# Uuu_sourcefile.net
KiCad netlist of a schematic drawn in EasyEDA Pro
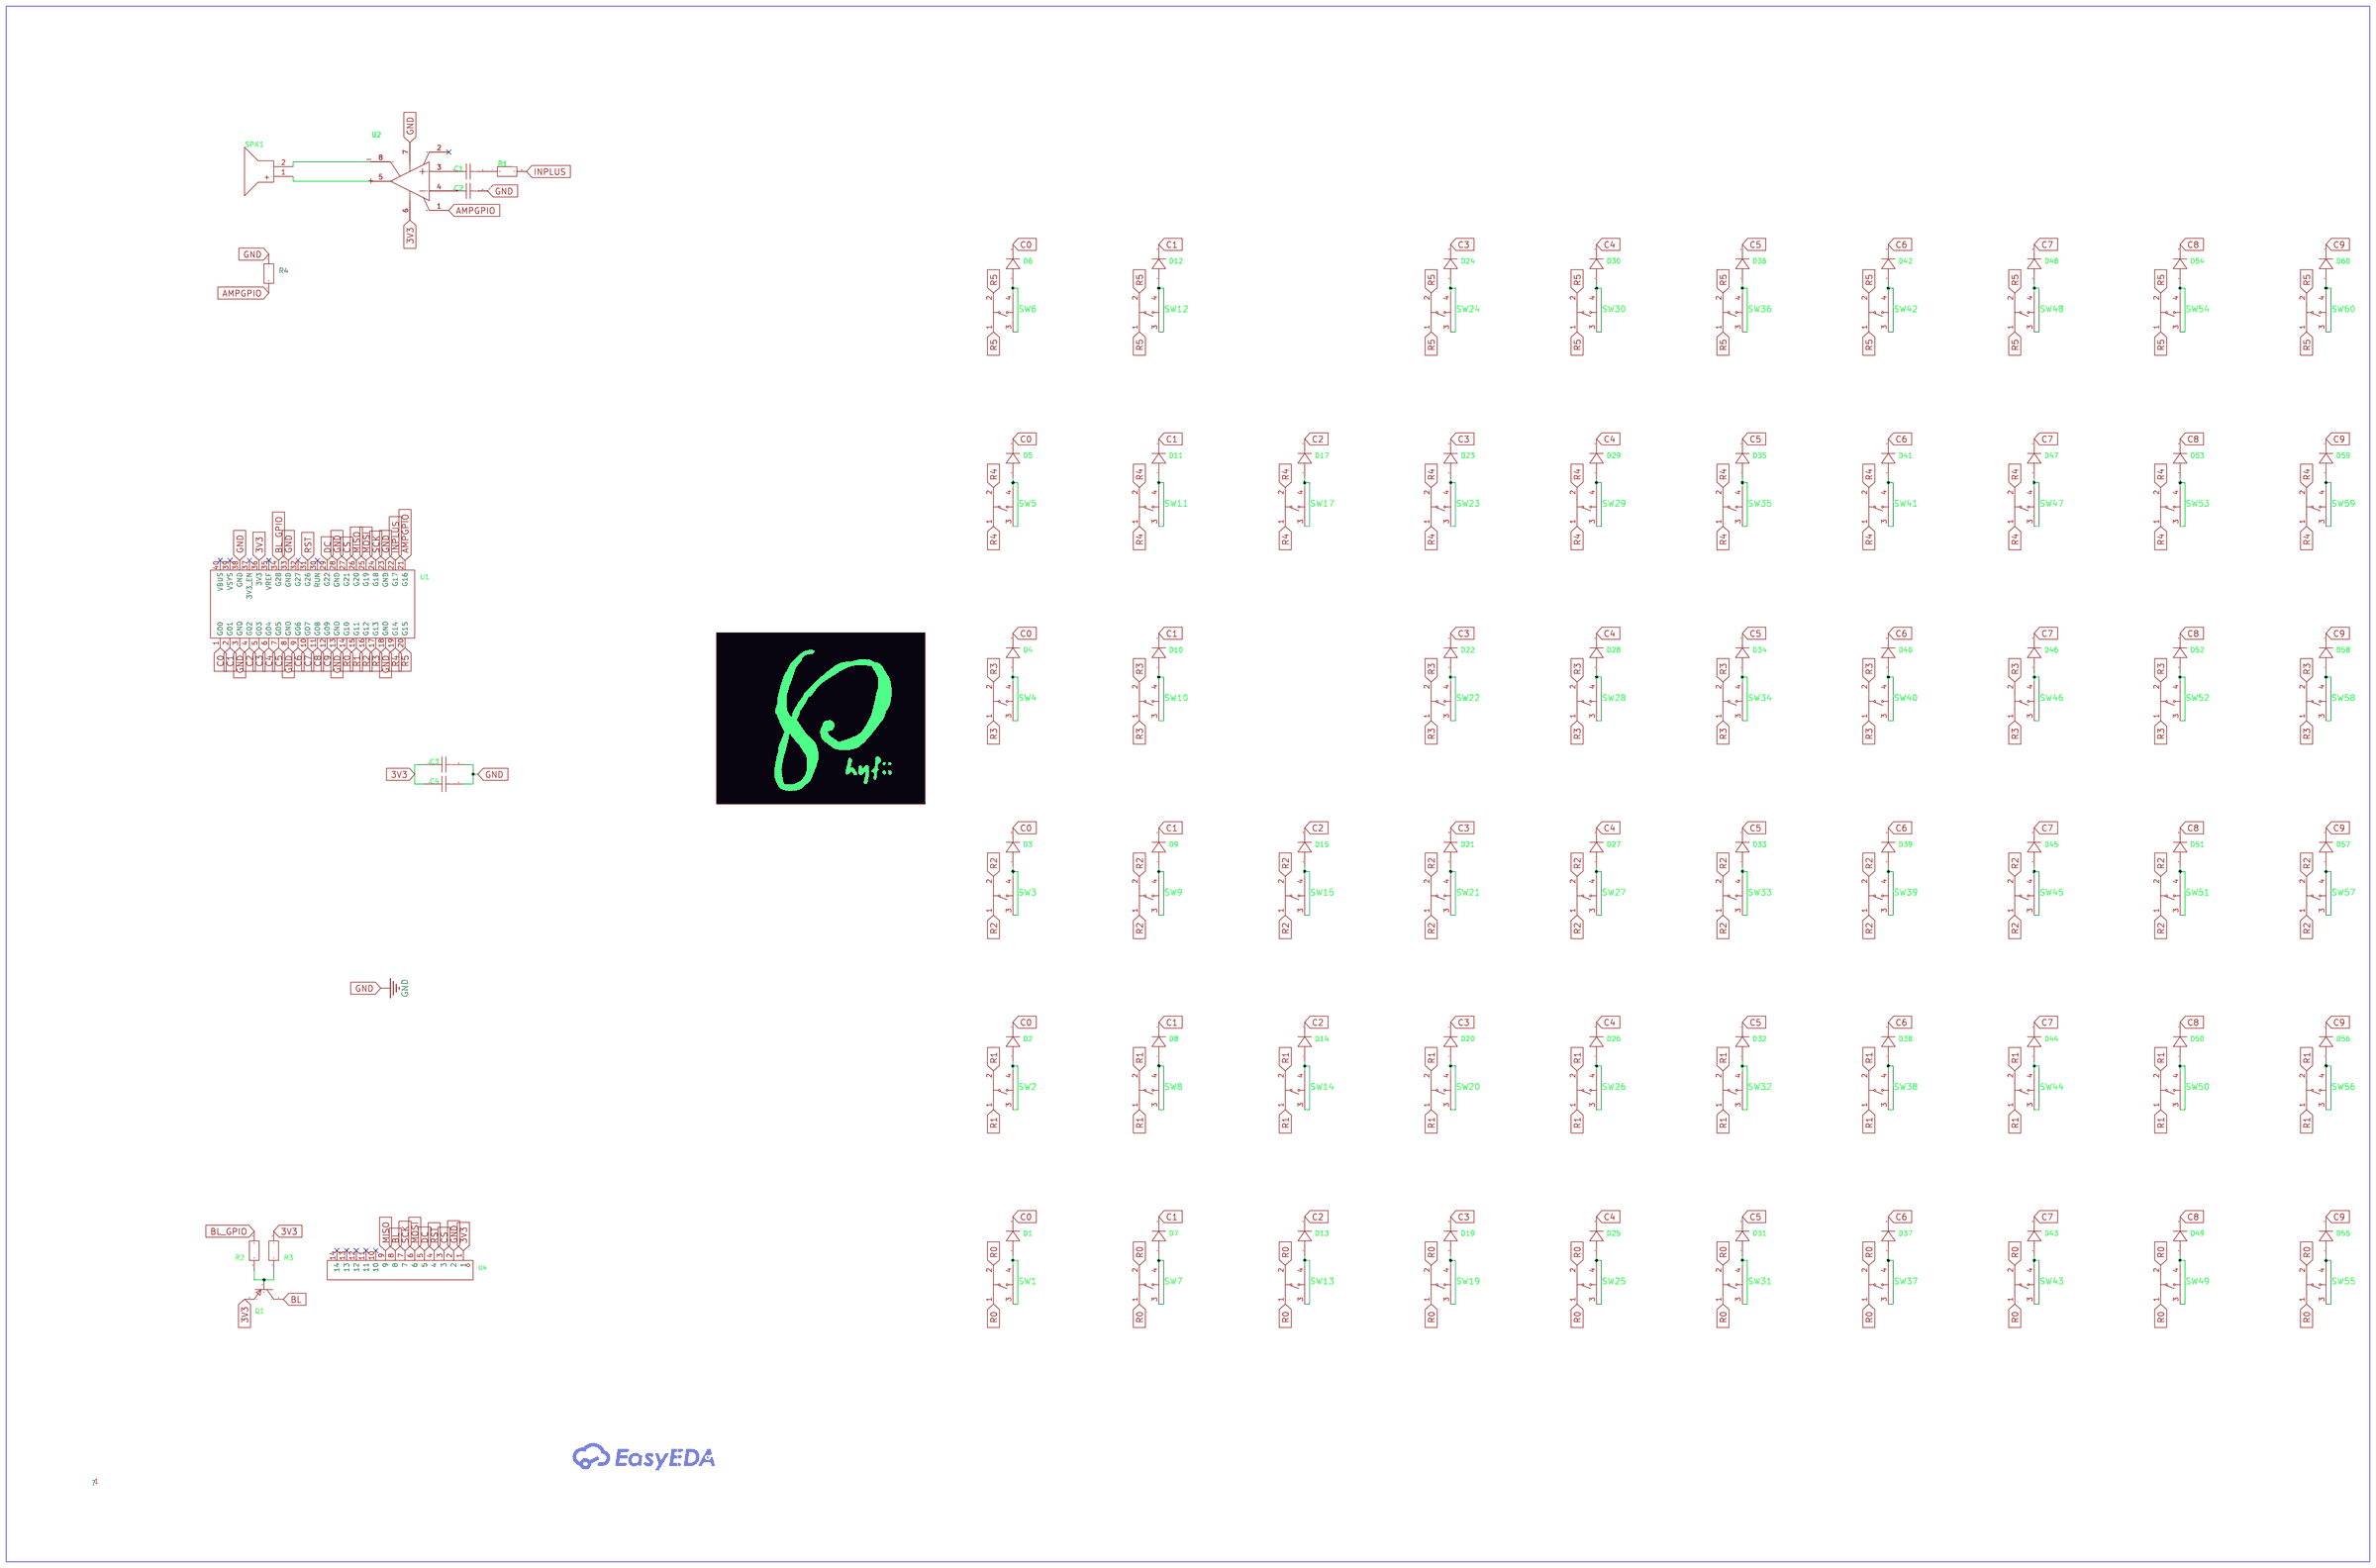
[diagram p0: schematic sheet]

(export (version "E")
  (design (tool "Eeschema 10.0.6"))
  (components
    (comp (ref "C1")
      (value "100nF")
      (footprint "easyedapro:C0603")
      (description "Capacitance:100nF Tolerance:±10% Tolerance:±10% Voltage Rating:50V Temperature Coefficient:X7R")
      (fields
        (field (name "Manufacturer Part") "CGA0603X7R104K500JT")
        (field (name "Manufacturer") "HRE(芯声)")
      )
      (libsource (lib "easyedapro") (part "CGA0603X7R104K500JT"))
    )
    (comp (ref "C2")
      (value "100nF")
      (footprint "easyedapro:C0603")
      (description "Capacitance:100nF Tolerance:±10% Tolerance:±10% Voltage Rating:50V Temperature Coefficient:X7R")
      (fields
        (field (name "Manufacturer Part") "CGA0603X7R104K500JT")
        (field (name "Manufacturer") "HRE(芯声)")
      )
      (libsource (lib "easyedapro") (part "CGA0603X7R104K500JT"))
    )
    (comp (ref "C3")
      (value "1uF")
      (footprint "easyedapro:C0603")
      (description "Capacitance:1uF Tolerance:±10% Tolerance:±10% Voltage Rating:50V Temperature Coefficient:X5R")
      (fields
        (field (name "Manufacturer Part") "CGA0603X5R105K500JT")
        (field (name "Manufacturer") "HRE(芯声)")
      )
      (libsource (lib "easyedapro") (part "CGA0603X5R105K500JT"))
    )
    (comp (ref "C4")
      (value "10uF")
      (footprint "easyedapro:C0603")
      (description "Capacitance:10uF Tolerance:±10% Tolerance:±10% Voltage Rating:10V Temperature Coefficient:X5R")
      (fields
        (field (name "Manufacturer Part") "CGA0603X5R106K100JT")
        (field (name "Manufacturer") "HRE(芯声)")
      )
      (libsource (lib "easyedapro") (part "CGA0603X5R106K100JT"))
    )
    (comp (ref "D1")
      (value "1N4148")
      (footprint "easyedapro:DO-35_BD2.2-L4.0-D0.50_1N4148")
      (fields (field (name "Manufacturer") "LJ(朗捷)"))
      (libsource (lib "easyedapro") (part "1N4148_C18195411"))
    )
    (comp (ref "D2")
      (value "1N4148")
      (footprint "easyedapro:DO-35_BD2.2-L4.0-D0.50_1N4148")
      (fields (field (name "Manufacturer") "LJ(朗捷)"))
      (libsource (lib "easyedapro") (part "1N4148_C18195411"))
    )
    (comp (ref "D3")
      (value "1N4148")
      (footprint "easyedapro:DO-35_BD2.2-L4.0-D0.50_1N4148")
      (fields (field (name "Manufacturer") "LJ(朗捷)"))
      (libsource (lib "easyedapro") (part "1N4148_C18195411"))
    )
    (comp (ref "D4")
      (value "1N4148")
      (footprint "easyedapro:DO-35_BD2.2-L4.0-D0.50_1N4148")
      (fields (field (name "Manufacturer") "LJ(朗捷)"))
      (libsource (lib "easyedapro") (part "1N4148_C18195411"))
    )
    (comp (ref "D5")
      (value "1N4148")
      (footprint "easyedapro:DO-35_BD2.2-L4.0-D0.50_1N4148")
      (fields (field (name "Manufacturer") "LJ(朗捷)"))
      (libsource (lib "easyedapro") (part "1N4148_C18195411"))
    )
    (comp (ref "D6")
      (value "1N4148")
      (footprint "easyedapro:DO-35_BD2.2-L4.0-D0.50_1N4148")
      (fields (field (name "Manufacturer") "LJ(朗捷)"))
      (libsource (lib "easyedapro") (part "1N4148_C18195411"))
    )
    (comp (ref "D7")
      (value "1N4148")
      (footprint "easyedapro:DO-35_BD2.2-L4.0-D0.50_1N4148")
      (fields (field (name "Manufacturer") "LJ(朗捷)"))
      (libsource (lib "easyedapro") (part "1N4148_C18195411"))
    )
    (comp (ref "D8")
      (value "1N4148")
      (footprint "easyedapro:DO-35_BD2.2-L4.0-D0.50_1N4148")
      (fields (field (name "Manufacturer") "LJ(朗捷)"))
      (libsource (lib "easyedapro") (part "1N4148_C18195411"))
    )
    (comp (ref "D9")
      (value "1N4148")
      (footprint "easyedapro:DO-35_BD2.2-L4.0-D0.50_1N4148")
      (fields (field (name "Manufacturer") "LJ(朗捷)"))
      (libsource (lib "easyedapro") (part "1N4148_C18195411"))
    )
    (comp (ref "D10")
      (value "1N4148")
      (footprint "easyedapro:DO-35_BD2.2-L4.0-D0.50_1N4148")
      (fields (field (name "Manufacturer") "LJ(朗捷)"))
      (libsource (lib "easyedapro") (part "1N4148_C18195411"))
    )
    (comp (ref "D11")
      (value "1N4148")
      (footprint "easyedapro:DO-35_BD2.2-L4.0-D0.50_1N4148")
      (fields (field (name "Manufacturer") "LJ(朗捷)"))
      (libsource (lib "easyedapro") (part "1N4148_C18195411"))
    )
    (comp (ref "D12")
      (value "1N4148")
      (footprint "easyedapro:DO-35_BD2.2-L4.0-D0.50_1N4148")
      (fields (field (name "Manufacturer") "LJ(朗捷)"))
      (libsource (lib "easyedapro") (part "1N4148_C18195411"))
    )
    (comp (ref "D13")
      (value "1N4148")
      (footprint "easyedapro:DO-35_BD2.2-L4.0-D0.50_1N4148")
      (fields (field (name "Manufacturer") "LJ(朗捷)"))
      (libsource (lib "easyedapro") (part "1N4148_C18195411"))
    )
    (comp (ref "D14")
      (value "1N4148")
      (footprint "easyedapro:DO-35_BD2.2-L4.0-D0.50_1N4148")
      (fields (field (name "Manufacturer") "LJ(朗捷)"))
      (libsource (lib "easyedapro") (part "1N4148_C18195411"))
    )
    (comp (ref "D15")
      (value "1N4148")
      (footprint "easyedapro:DO-35_BD2.2-L4.0-D0.50_1N4148")
      (fields (field (name "Manufacturer") "LJ(朗捷)"))
      (libsource (lib "easyedapro") (part "1N4148_C18195411"))
    )
    (comp (ref "D17")
      (value "1N4148")
      (footprint "easyedapro:DO-35_BD2.2-L4.0-D0.50_1N4148")
      (fields (field (name "Manufacturer") "LJ(朗捷)"))
      (libsource (lib "easyedapro") (part "1N4148_C18195411"))
    )
    (comp (ref "D19")
      (value "1N4148")
      (footprint "easyedapro:DO-35_BD2.2-L4.0-D0.50_1N4148")
      (fields (field (name "Manufacturer") "LJ(朗捷)"))
      (libsource (lib "easyedapro") (part "1N4148_C18195411"))
    )
    (comp (ref "D20")
      (value "1N4148")
      (footprint "easyedapro:DO-35_BD2.2-L4.0-D0.50_1N4148")
      (fields (field (name "Manufacturer") "LJ(朗捷)"))
      (libsource (lib "easyedapro") (part "1N4148_C18195411"))
    )
    (comp (ref "D21")
      (value "1N4148")
      (footprint "easyedapro:DO-35_BD2.2-L4.0-D0.50_1N4148")
      (fields (field (name "Manufacturer") "LJ(朗捷)"))
      (libsource (lib "easyedapro") (part "1N4148_C18195411"))
    )
    (comp (ref "D22")
      (value "1N4148")
      (footprint "easyedapro:DO-35_BD2.2-L4.0-D0.50_1N4148")
      (fields (field (name "Manufacturer") "LJ(朗捷)"))
      (libsource (lib "easyedapro") (part "1N4148_C18195411"))
    )
    (comp (ref "D23")
      (value "1N4148")
      (footprint "easyedapro:DO-35_BD2.2-L4.0-D0.50_1N4148")
      (fields (field (name "Manufacturer") "LJ(朗捷)"))
      (libsource (lib "easyedapro") (part "1N4148_C18195411"))
    )
    (comp (ref "D24")
      (value "1N4148")
      (footprint "easyedapro:DO-35_BD2.2-L4.0-D0.50_1N4148")
      (fields (field (name "Manufacturer") "LJ(朗捷)"))
      (libsource (lib "easyedapro") (part "1N4148_C18195411"))
    )
    (comp (ref "D25")
      (value "1N4148")
      (footprint "easyedapro:DO-35_BD2.2-L4.0-D0.50_1N4148")
      (fields (field (name "Manufacturer") "LJ(朗捷)"))
      (libsource (lib "easyedapro") (part "1N4148_C18195411"))
    )
    (comp (ref "D26")
      (value "1N4148")
      (footprint "easyedapro:DO-35_BD2.2-L4.0-D0.50_1N4148")
      (fields (field (name "Manufacturer") "LJ(朗捷)"))
      (libsource (lib "easyedapro") (part "1N4148_C18195411"))
    )
    (comp (ref "D27")
      (value "1N4148")
      (footprint "easyedapro:DO-35_BD2.2-L4.0-D0.50_1N4148")
      (fields (field (name "Manufacturer") "LJ(朗捷)"))
      (libsource (lib "easyedapro") (part "1N4148_C18195411"))
    )
    (comp (ref "D28")
      (value "1N4148")
      (footprint "easyedapro:DO-35_BD2.2-L4.0-D0.50_1N4148")
      (fields (field (name "Manufacturer") "LJ(朗捷)"))
      (libsource (lib "easyedapro") (part "1N4148_C18195411"))
    )
    (comp (ref "D29")
      (value "1N4148")
      (footprint "easyedapro:DO-35_BD2.2-L4.0-D0.50_1N4148")
      (fields (field (name "Manufacturer") "LJ(朗捷)"))
      (libsource (lib "easyedapro") (part "1N4148_C18195411"))
    )
    (comp (ref "D30")
      (value "1N4148")
      (footprint "easyedapro:DO-35_BD2.2-L4.0-D0.50_1N4148")
      (fields (field (name "Manufacturer") "LJ(朗捷)"))
      (libsource (lib "easyedapro") (part "1N4148_C18195411"))
    )
    (comp (ref "D31")
      (value "1N4148")
      (footprint "easyedapro:DO-35_BD2.2-L4.0-D0.50_1N4148")
      (fields (field (name "Manufacturer") "LJ(朗捷)"))
      (libsource (lib "easyedapro") (part "1N4148_C18195411"))
    )
    (comp (ref "D32")
      (value "1N4148")
      (footprint "easyedapro:DO-35_BD2.2-L4.0-D0.50_1N4148")
      (fields (field (name "Manufacturer") "LJ(朗捷)"))
      (libsource (lib "easyedapro") (part "1N4148_C18195411"))
    )
    (comp (ref "D33")
      (value "1N4148")
      (footprint "easyedapro:DO-35_BD2.2-L4.0-D0.50_1N4148")
      (fields (field (name "Manufacturer") "LJ(朗捷)"))
      (libsource (lib "easyedapro") (part "1N4148_C18195411"))
    )
    (comp (ref "D34")
      (value "1N4148")
      (footprint "easyedapro:DO-35_BD2.2-L4.0-D0.50_1N4148")
      (fields (field (name "Manufacturer") "LJ(朗捷)"))
      (libsource (lib "easyedapro") (part "1N4148_C18195411"))
    )
    (comp (ref "D35")
      (value "1N4148")
      (footprint "easyedapro:DO-35_BD2.2-L4.0-D0.50_1N4148")
      (fields (field (name "Manufacturer") "LJ(朗捷)"))
      (libsource (lib "easyedapro") (part "1N4148_C18195411"))
    )
    (comp (ref "D36")
      (value "1N4148")
      (footprint "easyedapro:DO-35_BD2.2-L4.0-D0.50_1N4148")
      (fields (field (name "Manufacturer") "LJ(朗捷)"))
      (libsource (lib "easyedapro") (part "1N4148_C18195411"))
    )
    (comp (ref "D37")
      (value "1N4148")
      (footprint "easyedapro:DO-35_BD2.2-L4.0-D0.50_1N4148")
      (fields (field (name "Manufacturer") "LJ(朗捷)"))
      (libsource (lib "easyedapro") (part "1N4148_C18195411"))
    )
    (comp (ref "D38")
      (value "1N4148")
      (footprint "easyedapro:DO-35_BD2.2-L4.0-D0.50_1N4148")
      (fields (field (name "Manufacturer") "LJ(朗捷)"))
      (libsource (lib "easyedapro") (part "1N4148_C18195411"))
    )
    (comp (ref "D39")
      (value "1N4148")
      (footprint "easyedapro:DO-35_BD2.2-L4.0-D0.50_1N4148")
      (fields (field (name "Manufacturer") "LJ(朗捷)"))
      (libsource (lib "easyedapro") (part "1N4148_C18195411"))
    )
    (comp (ref "D40")
      (value "1N4148")
      (footprint "easyedapro:DO-35_BD2.2-L4.0-D0.50_1N4148")
      (fields (field (name "Manufacturer") "LJ(朗捷)"))
      (libsource (lib "easyedapro") (part "1N4148_C18195411"))
    )
    (comp (ref "D41")
      (value "1N4148")
      (footprint "easyedapro:DO-35_BD2.2-L4.0-D0.50_1N4148")
      (fields (field (name "Manufacturer") "LJ(朗捷)"))
      (libsource (lib "easyedapro") (part "1N4148_C18195411"))
    )
    (comp (ref "D42")
      (value "1N4148")
      (footprint "easyedapro:DO-35_BD2.2-L4.0-D0.50_1N4148")
      (fields (field (name "Manufacturer") "LJ(朗捷)"))
      (libsource (lib "easyedapro") (part "1N4148_C18195411"))
    )
    (comp (ref "D43")
      (value "1N4148")
      (footprint "easyedapro:DO-35_BD2.2-L4.0-D0.50_1N4148")
      (fields (field (name "Manufacturer") "LJ(朗捷)"))
      (libsource (lib "easyedapro") (part "1N4148_C18195411"))
    )
    (comp (ref "D44")
      (value "1N4148")
      (footprint "easyedapro:DO-35_BD2.2-L4.0-D0.50_1N4148")
      (fields (field (name "Manufacturer") "LJ(朗捷)"))
      (libsource (lib "easyedapro") (part "1N4148_C18195411"))
    )
    (comp (ref "D45")
      (value "1N4148")
      (footprint "easyedapro:DO-35_BD2.2-L4.0-D0.50_1N4148")
      (fields (field (name "Manufacturer") "LJ(朗捷)"))
      (libsource (lib "easyedapro") (part "1N4148_C18195411"))
    )
    (comp (ref "D46")
      (value "1N4148")
      (footprint "easyedapro:DO-35_BD2.2-L4.0-D0.50_1N4148")
      (fields (field (name "Manufacturer") "LJ(朗捷)"))
      (libsource (lib "easyedapro") (part "1N4148_C18195411"))
    )
    (comp (ref "D47")
      (value "1N4148")
      (footprint "easyedapro:DO-35_BD2.2-L4.0-D0.50_1N4148")
      (fields (field (name "Manufacturer") "LJ(朗捷)"))
      (libsource (lib "easyedapro") (part "1N4148_C18195411"))
    )
    (comp (ref "D48")
      (value "1N4148")
      (footprint "easyedapro:DO-35_BD2.2-L4.0-D0.50_1N4148")
      (fields (field (name "Manufacturer") "LJ(朗捷)"))
      (libsource (lib "easyedapro") (part "1N4148_C18195411"))
    )
    (comp (ref "D49")
      (value "1N4148")
      (footprint "easyedapro:DO-35_BD2.2-L4.0-D0.50_1N4148")
      (fields (field (name "Manufacturer") "LJ(朗捷)"))
      (libsource (lib "easyedapro") (part "1N4148_C18195411"))
    )
    (comp (ref "D50")
      (value "1N4148")
      (footprint "easyedapro:DO-35_BD2.2-L4.0-D0.50_1N4148")
      (fields (field (name "Manufacturer") "LJ(朗捷)"))
      (libsource (lib "easyedapro") (part "1N4148_C18195411"))
    )
    (comp (ref "D51")
      (value "1N4148")
      (footprint "easyedapro:DO-35_BD2.2-L4.0-D0.50_1N4148")
      (fields (field (name "Manufacturer") "LJ(朗捷)"))
      (libsource (lib "easyedapro") (part "1N4148_C18195411"))
    )
    (comp (ref "D52")
      (value "1N4148")
      (footprint "easyedapro:DO-35_BD2.2-L4.0-D0.50_1N4148")
      (fields (field (name "Manufacturer") "LJ(朗捷)"))
      (libsource (lib "easyedapro") (part "1N4148_C18195411"))
    )
    (comp (ref "D53")
      (value "1N4148")
      (footprint "easyedapro:DO-35_BD2.2-L4.0-D0.50_1N4148")
      (fields (field (name "Manufacturer") "LJ(朗捷)"))
      (libsource (lib "easyedapro") (part "1N4148_C18195411"))
    )
    (comp (ref "D54")
      (value "1N4148")
      (footprint "easyedapro:DO-35_BD2.2-L4.0-D0.50_1N4148")
      (fields (field (name "Manufacturer") "LJ(朗捷)"))
      (libsource (lib "easyedapro") (part "1N4148_C18195411"))
    )
    (comp (ref "D55")
      (value "1N4148")
      (footprint "easyedapro:DO-35_BD2.2-L4.0-D0.50_1N4148")
      (fields (field (name "Manufacturer") "LJ(朗捷)"))
      (libsource (lib "easyedapro") (part "1N4148_C18195411"))
    )
    (comp (ref "D56")
      (value "1N4148")
      (footprint "easyedapro:DO-35_BD2.2-L4.0-D0.50_1N4148")
      (fields (field (name "Manufacturer") "LJ(朗捷)"))
      (libsource (lib "easyedapro") (part "1N4148_C18195411"))
    )
    (comp (ref "D57")
      (value "1N4148")
      (footprint "easyedapro:DO-35_BD2.2-L4.0-D0.50_1N4148")
      (fields (field (name "Manufacturer") "LJ(朗捷)"))
      (libsource (lib "easyedapro") (part "1N4148_C18195411"))
    )
    (comp (ref "D58")
      (value "1N4148")
      (footprint "easyedapro:DO-35_BD2.2-L4.0-D0.50_1N4148")
      (fields (field (name "Manufacturer") "LJ(朗捷)"))
      (libsource (lib "easyedapro") (part "1N4148_C18195411"))
    )
    (comp (ref "D59")
      (value "1N4148")
      (footprint "easyedapro:DO-35_BD2.2-L4.0-D0.50_1N4148")
      (fields (field (name "Manufacturer") "LJ(朗捷)"))
      (libsource (lib "easyedapro") (part "1N4148_C18195411"))
    )
    (comp (ref "D60")
      (value "1N4148")
      (footprint "easyedapro:DO-35_BD2.2-L4.0-D0.50_1N4148")
      (fields (field (name "Manufacturer") "LJ(朗捷)"))
      (libsource (lib "easyedapro") (part "1N4148_C18195411"))
    )
    (comp (ref "Q1")
      (value "MMBT3906")
      (footprint "easyedapro:SOT-23-3_L2.9-W1.3-P1.90-LS2.4-BR")
      (fields (field (name "Manufacturer") "XZT(信展通)"))
      (libsource (lib "easyedapro") (part "MMBT3906_C5805820"))
    )
    (comp (ref "R1")
      (value "1kΩ")
      (footprint "easyedapro:R0603")
      (fields (field (name "Manufacturer Part") "FRC0603J102 TS") (field (name "Manufacturer") "FOJAN(富捷)"))
      (libsource (lib "easyedapro") (part "FRC0603J102 TS"))
    )
    (comp (ref "R2")
      (value "10kΩ")
      (footprint "easyedapro:R0603")
      (fields (field (name "Manufacturer Part") "FRC0603F1002TS") (field (name "Manufacturer") "FOJAN(富捷)"))
      (libsource (lib "easyedapro") (part "FRC0603F1002TS"))
    )
    (comp (ref "R3")
      (value "100kΩ")
      (footprint "easyedapro:R0603")
      (fields (field (name "Manufacturer Part") "FRC0603J104 TS") (field (name "Manufacturer") "FOJAN(富捷)"))
      (libsource (lib "easyedapro") (part "FRC0603J104 TS"))
    )
    (comp (ref "R4")
      (value "100kΩ")
      (footprint "easyedapro:R0603")
      (fields (field (name "Manufacturer Part") "FRC0603J104 TS") (field (name "Manufacturer") "FOJAN(富捷)"))
      (libsource (lib "easyedapro") (part "FRC0603J104 TS"))
    )
    (comp (ref "SPK1")
      (value "2308 8Ω1w")
      (footprint "easyedapro:SPK-TH_BD23.0-P10.00-D0.8-L-RD")
      (fields (field (name "Manufacturer") "S&S(海旭)"))
      (libsource (lib "easyedapro") (part "2308 8Ω1W"))
    )
    (comp (ref "SW1")
      (value "TS-1095PS-A1B2-C3D2")
      (footprint "easyedapro:KEY-SMD_4P-L6.0-W6.0-P3.90-LS9.0")
      (fields (field (name "Manufacturer") "Yuandi(元迪)"))
      (libsource (lib "easyedapro") (part "TS-1095PS-A1B2-C3D2"))
    )
    (comp (ref "SW2")
      (value "TS-1095PS-A1B2-C3D2")
      (footprint "easyedapro:KEY-SMD_4P-L6.0-W6.0-P3.90-LS9.0")
      (fields (field (name "Manufacturer") "Yuandi(元迪)"))
      (libsource (lib "easyedapro") (part "TS-1095PS-A1B2-C3D2"))
    )
    (comp (ref "SW3")
      (value "TS-1095PS-A1B2-C3D2")
      (footprint "easyedapro:KEY-SMD_4P-L6.0-W6.0-P3.90-LS9.0")
      (fields (field (name "Manufacturer") "Yuandi(元迪)"))
      (libsource (lib "easyedapro") (part "TS-1095PS-A1B2-C3D2"))
    )
    (comp (ref "SW4")
      (value "TS-1095PS-A1B2-C3D2")
      (footprint "easyedapro:KEY-SMD_4P-L6.0-W6.0-P3.90-LS9.0")
      (fields (field (name "Manufacturer") "Yuandi(元迪)"))
      (libsource (lib "easyedapro") (part "TS-1095PS-A1B2-C3D2"))
    )
    (comp (ref "SW5")
      (value "TS-1095PS-A1B2-C3D2")
      (footprint "easyedapro:KEY-SMD_4P-L6.0-W6.0-P3.90-LS9.0")
      (fields (field (name "Manufacturer") "Yuandi(元迪)"))
      (libsource (lib "easyedapro") (part "TS-1095PS-A1B2-C3D2"))
    )
    (comp (ref "SW6")
      (value "TS-1095PS-A1B2-C3D2")
      (footprint "easyedapro:KEY-SMD_4P-L6.0-W6.0-P3.90-LS9.0")
      (fields (field (name "Manufacturer") "Yuandi(元迪)"))
      (libsource (lib "easyedapro") (part "TS-1095PS-A1B2-C3D2"))
    )
    (comp (ref "SW7")
      (value "TS-1095PS-A1B2-C3D2")
      (footprint "easyedapro:KEY-SMD_4P-L6.0-W6.0-P3.90-LS9.0")
      (fields (field (name "Manufacturer") "Yuandi(元迪)"))
      (libsource (lib "easyedapro") (part "TS-1095PS-A1B2-C3D2"))
    )
    (comp (ref "SW8")
      (value "TS-1095PS-A1B2-C3D2")
      (footprint "easyedapro:KEY-SMD_4P-L6.0-W6.0-P3.90-LS9.0")
      (fields (field (name "Manufacturer") "Yuandi(元迪)"))
      (libsource (lib "easyedapro") (part "TS-1095PS-A1B2-C3D2"))
    )
    (comp (ref "SW9")
      (value "TS-1095PS-A1B2-C3D2")
      (footprint "easyedapro:KEY-SMD_4P-L6.0-W6.0-P3.90-LS9.0")
      (fields (field (name "Manufacturer") "Yuandi(元迪)"))
      (libsource (lib "easyedapro") (part "TS-1095PS-A1B2-C3D2"))
    )
    (comp (ref "SW10")
      (value "TS-1095PS-A1B2-C3D2")
      (footprint "easyedapro:KEY-SMD_4P-L6.0-W6.0-P3.90-LS9.0")
      (fields (field (name "Manufacturer") "Yuandi(元迪)"))
      (libsource (lib "easyedapro") (part "TS-1095PS-A1B2-C3D2"))
    )
    (comp (ref "SW11")
      (value "TS-1095PS-A1B2-C3D2")
      (footprint "easyedapro:KEY-SMD_4P-L6.0-W6.0-P3.90-LS9.0")
      (fields (field (name "Manufacturer") "Yuandi(元迪)"))
      (libsource (lib "easyedapro") (part "TS-1095PS-A1B2-C3D2"))
    )
    (comp (ref "SW12")
      (value "TS-1095PS-A1B2-C3D2")
      (footprint "easyedapro:KEY-SMD_4P-L6.0-W6.0-P3.90-LS9.0")
      (fields (field (name "Manufacturer") "Yuandi(元迪)"))
      (libsource (lib "easyedapro") (part "TS-1095PS-A1B2-C3D2"))
    )
    (comp (ref "SW13")
      (value "TS-1095PS-A1B2-C3D2")
      (footprint "easyedapro:KEY-SMD_4P-L6.0-W6.0-P3.90-LS9.0")
      (fields (field (name "Manufacturer") "Yuandi(元迪)"))
      (libsource (lib "easyedapro") (part "TS-1095PS-A1B2-C3D2"))
    )
    (comp (ref "SW14")
      (value "TS-1095PS-A1B2-C3D2")
      (footprint "easyedapro:KEY-SMD_4P-L6.0-W6.0-P3.90-LS9.0")
      (fields (field (name "Manufacturer") "Yuandi(元迪)"))
      (libsource (lib "easyedapro") (part "TS-1095PS-A1B2-C3D2"))
    )
    (comp (ref "SW15")
      (value "TS-1095PS-A1B2-C3D2")
      (footprint "easyedapro:KEY-SMD_4P-L6.0-W6.0-P3.90-LS9.0")
      (fields (field (name "Manufacturer") "Yuandi(元迪)"))
      (libsource (lib "easyedapro") (part "TS-1095PS-A1B2-C3D2"))
    )
    (comp (ref "SW17")
      (value "TS-1095PS-A1B2-C3D2")
      (footprint "easyedapro:KEY-SMD_4P-L6.0-W6.0-P3.90-LS9.0")
      (fields (field (name "Manufacturer") "Yuandi(元迪)"))
      (libsource (lib "easyedapro") (part "TS-1095PS-A1B2-C3D2"))
    )
    (comp (ref "SW19")
      (value "TS-1095PS-A1B2-C3D2")
      (footprint "easyedapro:KEY-SMD_4P-L6.0-W6.0-P3.90-LS9.0")
      (fields (field (name "Manufacturer") "Yuandi(元迪)"))
      (libsource (lib "easyedapro") (part "TS-1095PS-A1B2-C3D2"))
    )
    (comp (ref "SW20")
      (value "TS-1095PS-A1B2-C3D2")
      (footprint "easyedapro:KEY-SMD_4P-L6.0-W6.0-P3.90-LS9.0")
      (fields (field (name "Manufacturer") "Yuandi(元迪)"))
      (libsource (lib "easyedapro") (part "TS-1095PS-A1B2-C3D2"))
    )
    (comp (ref "SW21")
      (value "TS-1095PS-A1B2-C3D2")
      (footprint "easyedapro:KEY-SMD_4P-L6.0-W6.0-P3.90-LS9.0")
      (fields (field (name "Manufacturer") "Yuandi(元迪)"))
      (libsource (lib "easyedapro") (part "TS-1095PS-A1B2-C3D2"))
    )
    (comp (ref "SW22")
      (value "TS-1095PS-A1B2-C3D2")
      (footprint "easyedapro:KEY-SMD_4P-L6.0-W6.0-P3.90-LS9.0")
      (fields (field (name "Manufacturer") "Yuandi(元迪)"))
      (libsource (lib "easyedapro") (part "TS-1095PS-A1B2-C3D2"))
    )
    (comp (ref "SW23")
      (value "TS-1095PS-A1B2-C3D2")
      (footprint "easyedapro:KEY-SMD_4P-L6.0-W6.0-P3.90-LS9.0")
      (fields (field (name "Manufacturer") "Yuandi(元迪)"))
      (libsource (lib "easyedapro") (part "TS-1095PS-A1B2-C3D2"))
    )
    (comp (ref "SW24")
      (value "TS-1095PS-A1B2-C3D2")
      (footprint "easyedapro:KEY-SMD_4P-L6.0-W6.0-P3.90-LS9.0")
      (fields (field (name "Manufacturer") "Yuandi(元迪)"))
      (libsource (lib "easyedapro") (part "TS-1095PS-A1B2-C3D2"))
    )
    (comp (ref "SW25")
      (value "TS-1095PS-A1B2-C3D2")
      (footprint "easyedapro:KEY-SMD_4P-L6.0-W6.0-P3.90-LS9.0")
      (fields (field (name "Manufacturer") "Yuandi(元迪)"))
      (libsource (lib "easyedapro") (part "TS-1095PS-A1B2-C3D2"))
    )
    (comp (ref "SW26")
      (value "TS-1095PS-A1B2-C3D2")
      (footprint "easyedapro:KEY-SMD_4P-L6.0-W6.0-P3.90-LS9.0")
      (fields (field (name "Manufacturer") "Yuandi(元迪)"))
      (libsource (lib "easyedapro") (part "TS-1095PS-A1B2-C3D2"))
    )
    (comp (ref "SW27")
      (value "TS-1095PS-A1B2-C3D2")
      (footprint "easyedapro:KEY-SMD_4P-L6.0-W6.0-P3.90-LS9.0")
      (fields (field (name "Manufacturer") "Yuandi(元迪)"))
      (libsource (lib "easyedapro") (part "TS-1095PS-A1B2-C3D2"))
    )
    (comp (ref "SW28")
      (value "TS-1095PS-A1B2-C3D2")
      (footprint "easyedapro:KEY-SMD_4P-L6.0-W6.0-P3.90-LS9.0")
      (fields (field (name "Manufacturer") "Yuandi(元迪)"))
      (libsource (lib "easyedapro") (part "TS-1095PS-A1B2-C3D2"))
    )
    (comp (ref "SW29")
      (value "TS-1095PS-A1B2-C3D2")
      (footprint "easyedapro:KEY-SMD_4P-L6.0-W6.0-P3.90-LS9.0")
      (fields (field (name "Manufacturer") "Yuandi(元迪)"))
      (libsource (lib "easyedapro") (part "TS-1095PS-A1B2-C3D2"))
    )
    (comp (ref "SW30")
      (value "TS-1095PS-A1B2-C3D2")
      (footprint "easyedapro:KEY-SMD_4P-L6.0-W6.0-P3.90-LS9.0")
      (fields (field (name "Manufacturer") "Yuandi(元迪)"))
      (libsource (lib "easyedapro") (part "TS-1095PS-A1B2-C3D2"))
    )
    (comp (ref "SW31")
      (value "TS-1095PS-A1B2-C3D2")
      (footprint "easyedapro:KEY-SMD_4P-L6.0-W6.0-P3.90-LS9.0")
      (fields (field (name "Manufacturer") "Yuandi(元迪)"))
      (libsource (lib "easyedapro") (part "TS-1095PS-A1B2-C3D2"))
    )
    (comp (ref "SW32")
      (value "TS-1095PS-A1B2-C3D2")
      (footprint "easyedapro:KEY-SMD_4P-L6.0-W6.0-P3.90-LS9.0")
      (fields (field (name "Manufacturer") "Yuandi(元迪)"))
      (libsource (lib "easyedapro") (part "TS-1095PS-A1B2-C3D2"))
    )
    (comp (ref "SW33")
      (value "TS-1095PS-A1B2-C3D2")
      (footprint "easyedapro:KEY-SMD_4P-L6.0-W6.0-P3.90-LS9.0")
      (fields (field (name "Manufacturer") "Yuandi(元迪)"))
      (libsource (lib "easyedapro") (part "TS-1095PS-A1B2-C3D2"))
    )
    (comp (ref "SW34")
      (value "TS-1095PS-A1B2-C3D2")
      (footprint "easyedapro:KEY-SMD_4P-L6.0-W6.0-P3.90-LS9.0")
      (fields (field (name "Manufacturer") "Yuandi(元迪)"))
      (libsource (lib "easyedapro") (part "TS-1095PS-A1B2-C3D2"))
    )
    (comp (ref "SW35")
      (value "TS-1095PS-A1B2-C3D2")
      (footprint "easyedapro:KEY-SMD_4P-L6.0-W6.0-P3.90-LS9.0")
      (fields (field (name "Manufacturer") "Yuandi(元迪)"))
      (libsource (lib "easyedapro") (part "TS-1095PS-A1B2-C3D2"))
    )
    (comp (ref "SW36")
      (value "TS-1095PS-A1B2-C3D2")
      (footprint "easyedapro:KEY-SMD_4P-L6.0-W6.0-P3.90-LS9.0")
      (fields (field (name "Manufacturer") "Yuandi(元迪)"))
      (libsource (lib "easyedapro") (part "TS-1095PS-A1B2-C3D2"))
    )
    (comp (ref "SW37")
      (value "TS-1095PS-A1B2-C3D2")
      (footprint "easyedapro:KEY-SMD_4P-L6.0-W6.0-P3.90-LS9.0")
      (fields (field (name "Manufacturer") "Yuandi(元迪)"))
      (libsource (lib "easyedapro") (part "TS-1095PS-A1B2-C3D2"))
    )
    (comp (ref "SW38")
      (value "TS-1095PS-A1B2-C3D2")
      (footprint "easyedapro:KEY-SMD_4P-L6.0-W6.0-P3.90-LS9.0")
      (fields (field (name "Manufacturer") "Yuandi(元迪)"))
      (libsource (lib "easyedapro") (part "TS-1095PS-A1B2-C3D2"))
    )
    (comp (ref "SW39")
      (value "TS-1095PS-A1B2-C3D2")
      (footprint "easyedapro:KEY-SMD_4P-L6.0-W6.0-P3.90-LS9.0")
      (fields (field (name "Manufacturer") "Yuandi(元迪)"))
      (libsource (lib "easyedapro") (part "TS-1095PS-A1B2-C3D2"))
    )
    (comp (ref "SW40")
      (value "TS-1095PS-A1B2-C3D2")
      (footprint "easyedapro:KEY-SMD_4P-L6.0-W6.0-P3.90-LS9.0")
      (fields (field (name "Manufacturer") "Yuandi(元迪)"))
      (libsource (lib "easyedapro") (part "TS-1095PS-A1B2-C3D2"))
    )
    (comp (ref "SW41")
      (value "TS-1095PS-A1B2-C3D2")
      (footprint "easyedapro:KEY-SMD_4P-L6.0-W6.0-P3.90-LS9.0")
      (fields (field (name "Manufacturer") "Yuandi(元迪)"))
      (libsource (lib "easyedapro") (part "TS-1095PS-A1B2-C3D2"))
    )
    (comp (ref "SW42")
      (value "TS-1095PS-A1B2-C3D2")
      (footprint "easyedapro:KEY-SMD_4P-L6.0-W6.0-P3.90-LS9.0")
      (fields (field (name "Manufacturer") "Yuandi(元迪)"))
      (libsource (lib "easyedapro") (part "TS-1095PS-A1B2-C3D2"))
    )
    (comp (ref "SW43")
      (value "TS-1095PS-A1B2-C3D2")
      (footprint "easyedapro:KEY-SMD_4P-L6.0-W6.0-P3.90-LS9.0")
      (fields (field (name "Manufacturer") "Yuandi(元迪)"))
      (libsource (lib "easyedapro") (part "TS-1095PS-A1B2-C3D2"))
    )
    (comp (ref "SW44")
      (value "TS-1095PS-A1B2-C3D2")
      (footprint "easyedapro:KEY-SMD_4P-L6.0-W6.0-P3.90-LS9.0")
      (fields (field (name "Manufacturer") "Yuandi(元迪)"))
      (libsource (lib "easyedapro") (part "TS-1095PS-A1B2-C3D2"))
    )
    (comp (ref "SW45")
      (value "TS-1095PS-A1B2-C3D2")
      (footprint "easyedapro:KEY-SMD_4P-L6.0-W6.0-P3.90-LS9.0")
      (fields (field (name "Manufacturer") "Yuandi(元迪)"))
      (libsource (lib "easyedapro") (part "TS-1095PS-A1B2-C3D2"))
    )
    (comp (ref "SW46")
      (value "TS-1095PS-A1B2-C3D2")
      (footprint "easyedapro:KEY-SMD_4P-L6.0-W6.0-P3.90-LS9.0")
      (fields (field (name "Manufacturer") "Yuandi(元迪)"))
      (libsource (lib "easyedapro") (part "TS-1095PS-A1B2-C3D2"))
    )
    (comp (ref "SW47")
      (value "TS-1095PS-A1B2-C3D2")
      (footprint "easyedapro:KEY-SMD_4P-L6.0-W6.0-P3.90-LS9.0")
      (fields (field (name "Manufacturer") "Yuandi(元迪)"))
      (libsource (lib "easyedapro") (part "TS-1095PS-A1B2-C3D2"))
    )
    (comp (ref "SW48")
      (value "TS-1095PS-A1B2-C3D2")
      (footprint "easyedapro:KEY-SMD_4P-L6.0-W6.0-P3.90-LS9.0")
      (fields (field (name "Manufacturer") "Yuandi(元迪)"))
      (libsource (lib "easyedapro") (part "TS-1095PS-A1B2-C3D2"))
    )
    (comp (ref "SW49")
      (value "TS-1095PS-A1B2-C3D2")
      (footprint "easyedapro:KEY-SMD_4P-L6.0-W6.0-P3.90-LS9.0")
      (fields (field (name "Manufacturer") "Yuandi(元迪)"))
      (libsource (lib "easyedapro") (part "TS-1095PS-A1B2-C3D2"))
    )
    (comp (ref "SW50")
      (value "TS-1095PS-A1B2-C3D2")
      (footprint "easyedapro:KEY-SMD_4P-L6.0-W6.0-P3.90-LS9.0")
      (fields (field (name "Manufacturer") "Yuandi(元迪)"))
      (libsource (lib "easyedapro") (part "TS-1095PS-A1B2-C3D2"))
    )
    (comp (ref "SW51")
      (value "TS-1095PS-A1B2-C3D2")
      (footprint "easyedapro:KEY-SMD_4P-L6.0-W6.0-P3.90-LS9.0")
      (fields (field (name "Manufacturer") "Yuandi(元迪)"))
      (libsource (lib "easyedapro") (part "TS-1095PS-A1B2-C3D2"))
    )
    (comp (ref "SW52")
      (value "TS-1095PS-A1B2-C3D2")
      (footprint "easyedapro:KEY-SMD_4P-L6.0-W6.0-P3.90-LS9.0")
      (fields (field (name "Manufacturer") "Yuandi(元迪)"))
      (libsource (lib "easyedapro") (part "TS-1095PS-A1B2-C3D2"))
    )
    (comp (ref "SW53")
      (value "TS-1095PS-A1B2-C3D2")
      (footprint "easyedapro:KEY-SMD_4P-L6.0-W6.0-P3.90-LS9.0")
      (fields (field (name "Manufacturer") "Yuandi(元迪)"))
      (libsource (lib "easyedapro") (part "TS-1095PS-A1B2-C3D2"))
    )
    (comp (ref "SW54")
      (value "TS-1095PS-A1B2-C3D2")
      (footprint "easyedapro:KEY-SMD_4P-L6.0-W6.0-P3.90-LS9.0")
      (fields (field (name "Manufacturer") "Yuandi(元迪)"))
      (libsource (lib "easyedapro") (part "TS-1095PS-A1B2-C3D2"))
    )
    (comp (ref "SW55")
      (value "TS-1095PS-A1B2-C3D2")
      (footprint "easyedapro:KEY-SMD_4P-L6.0-W6.0-P3.90-LS9.0")
      (fields (field (name "Manufacturer") "Yuandi(元迪)"))
      (libsource (lib "easyedapro") (part "TS-1095PS-A1B2-C3D2"))
    )
    (comp (ref "SW56")
      (value "TS-1095PS-A1B2-C3D2")
      (footprint "easyedapro:KEY-SMD_4P-L6.0-W6.0-P3.90-LS9.0")
      (fields (field (name "Manufacturer") "Yuandi(元迪)"))
      (libsource (lib "easyedapro") (part "TS-1095PS-A1B2-C3D2"))
    )
    (comp (ref "SW57")
      (value "TS-1095PS-A1B2-C3D2")
      (footprint "easyedapro:KEY-SMD_4P-L6.0-W6.0-P3.90-LS9.0")
      (fields (field (name "Manufacturer") "Yuandi(元迪)"))
      (libsource (lib "easyedapro") (part "TS-1095PS-A1B2-C3D2"))
    )
    (comp (ref "SW58")
      (value "TS-1095PS-A1B2-C3D2")
      (footprint "easyedapro:KEY-SMD_4P-L6.0-W6.0-P3.90-LS9.0")
      (fields (field (name "Manufacturer") "Yuandi(元迪)"))
      (libsource (lib "easyedapro") (part "TS-1095PS-A1B2-C3D2"))
    )
    (comp (ref "SW59")
      (value "TS-1095PS-A1B2-C3D2")
      (footprint "easyedapro:KEY-SMD_4P-L6.0-W6.0-P3.90-LS9.0")
      (fields (field (name "Manufacturer") "Yuandi(元迪)"))
      (libsource (lib "easyedapro") (part "TS-1095PS-A1B2-C3D2"))
    )
    (comp (ref "SW60")
      (value "TS-1095PS-A1B2-C3D2")
      (footprint "easyedapro:KEY-SMD_4P-L6.0-W6.0-P3.90-LS9.0")
      (fields (field (name "Manufacturer") "Yuandi(元迪)"))
      (libsource (lib "easyedapro") (part "TS-1095PS-A1B2-C3D2"))
    )
    (comp (ref "U1")
      (value "ColorEasyPico2-RP2350")
      (footprint "easyedapro:COMM-TH_COLOREASYPICO2-RP2350")
      (fields (field (name "Manufacturer") "立创开发板"))
      (libsource (lib "easyedapro") (part "COLOREASYPICO2-RP2350"))
    )
    (comp (ref "U2")
      (value "PAM8302AASCR")
      (footprint "easyedapro:MSOP-8_L3.0-W3.0-P0.65-LS5.0-BL")
      (fields (field (name "Manufacturer") "DIODES(美台)"))
      (libsource (lib "easyedapro") (part "PAM8302AASCR"))
    )
    (comp (ref "U4")
      (value "KH-2.54FH-1X14P-H8.5")
      (footprint "easyedapro:HDR-TH_14P-P2.54-V-F")
      (fields (field (name "Manufacturer") "kinghelm(金航标)"))
      (libsource (lib "easyedapro") (part "KH-2.54FH-1X14P-H8.5"))
    )
  )
  (nets
    (net (code "1") (name "3V3") (class "Default")
      (node (ref "C3") (pin "1") (pinfunction "1_1") (pintype "unspecified"))
      (node (ref "C4") (pin "1") (pinfunction "1_1") (pintype "unspecified"))
      (node (ref "Q1") (pin "2") (pinfunction "E_2") (pintype "unspecified"))
      (node (ref "R3") (pin "2") (pinfunction "2_2") (pintype "unspecified"))
      (node (ref "U1") (pin "36") (pinfunction "3V3_36") (pintype "unspecified"))
      (node (ref "U2") (pin "6") (pinfunction "VDD_6") (pintype "unspecified"))
      (node (ref "U4") (pin "1") (pinfunction "1_1") (pintype "input"))
    )
    (net (code "2") (name "AMPGPIO") (class "Default")
      (node (ref "R4") (pin "2") (pinfunction "2_2") (pintype "unspecified"))
      (node (ref "U1") (pin "21") (pinfunction "G16_21") (pintype "unspecified"))
      (node (ref "U2") (pin "1") (pinfunction "SD#_1") (pintype "unspecified"))
    )
    (net (code "3") (name "BL") (class "Default")
      (node (ref "Q1") (pin "3") (pinfunction "C_3") (pintype "unspecified"))
      (node (ref "U4") (pin "8") (pinfunction "8_8") (pintype "input"))
    )
    (net (code "4") (name "BL_GPIO") (class "Default")
      (node (ref "R2") (pin "2") (pinfunction "2_2") (pintype "unspecified"))
      (node (ref "U1") (pin "34") (pinfunction "G28_34") (pintype "unspecified"))
    )
    (net (code "5") (name "C0") (class "Default")
      (node (ref "D1") (pin "2") (pinfunction "C_2") (pintype "unspecified"))
      (node (ref "D2") (pin "2") (pinfunction "C_2") (pintype "unspecified"))
      (node (ref "D3") (pin "2") (pinfunction "C_2") (pintype "unspecified"))
      (node (ref "D4") (pin "2") (pinfunction "C_2") (pintype "unspecified"))
      (node (ref "D5") (pin "2") (pinfunction "C_2") (pintype "unspecified"))
      (node (ref "D6") (pin "2") (pinfunction "C_2") (pintype "unspecified"))
      (node (ref "U1") (pin "1") (pinfunction "G00_1") (pintype "unspecified"))
    )
    (net (code "6") (name "C1") (class "Default")
      (node (ref "D10") (pin "2") (pinfunction "C_2") (pintype "unspecified"))
      (node (ref "D11") (pin "2") (pinfunction "C_2") (pintype "unspecified"))
      (node (ref "D12") (pin "2") (pinfunction "C_2") (pintype "unspecified"))
      (node (ref "D7") (pin "2") (pinfunction "C_2") (pintype "unspecified"))
      (node (ref "D8") (pin "2") (pinfunction "C_2") (pintype "unspecified"))
      (node (ref "D9") (pin "2") (pinfunction "C_2") (pintype "unspecified"))
      (node (ref "U1") (pin "2") (pinfunction "G01_2") (pintype "unspecified"))
    )
    (net (code "7") (name "C2") (class "Default")
      (node (ref "D13") (pin "2") (pinfunction "C_2") (pintype "unspecified"))
      (node (ref "D14") (pin "2") (pinfunction "C_2") (pintype "unspecified"))
      (node (ref "D15") (pin "2") (pinfunction "C_2") (pintype "unspecified"))
      (node (ref "D17") (pin "2") (pinfunction "C_2") (pintype "unspecified"))
      (node (ref "U1") (pin "4") (pinfunction "G02_4") (pintype "unspecified"))
    )
    (net (code "8") (name "C3") (class "Default")
      (node (ref "D19") (pin "2") (pinfunction "C_2") (pintype "unspecified"))
      (node (ref "D20") (pin "2") (pinfunction "C_2") (pintype "unspecified"))
      (node (ref "D21") (pin "2") (pinfunction "C_2") (pintype "unspecified"))
      (node (ref "D22") (pin "2") (pinfunction "C_2") (pintype "unspecified"))
      (node (ref "D23") (pin "2") (pinfunction "C_2") (pintype "unspecified"))
      (node (ref "D24") (pin "2") (pinfunction "C_2") (pintype "unspecified"))
      (node (ref "U1") (pin "5") (pinfunction "G03_5") (pintype "unspecified"))
    )
    (net (code "9") (name "C4") (class "Default")
      (node (ref "D25") (pin "2") (pinfunction "C_2") (pintype "unspecified"))
      (node (ref "D26") (pin "2") (pinfunction "C_2") (pintype "unspecified"))
      (node (ref "D27") (pin "2") (pinfunction "C_2") (pintype "unspecified"))
      (node (ref "D28") (pin "2") (pinfunction "C_2") (pintype "unspecified"))
      (node (ref "D29") (pin "2") (pinfunction "C_2") (pintype "unspecified"))
      (node (ref "D30") (pin "2") (pinfunction "C_2") (pintype "unspecified"))
      (node (ref "U1") (pin "6") (pinfunction "G04_6") (pintype "unspecified"))
    )
    (net (code "10") (name "C5") (class "Default")
      (node (ref "D31") (pin "2") (pinfunction "C_2") (pintype "unspecified"))
      (node (ref "D32") (pin "2") (pinfunction "C_2") (pintype "unspecified"))
      (node (ref "D33") (pin "2") (pinfunction "C_2") (pintype "unspecified"))
      (node (ref "D34") (pin "2") (pinfunction "C_2") (pintype "unspecified"))
      (node (ref "D35") (pin "2") (pinfunction "C_2") (pintype "unspecified"))
      (node (ref "D36") (pin "2") (pinfunction "C_2") (pintype "unspecified"))
      (node (ref "U1") (pin "7") (pinfunction "G05_7") (pintype "unspecified"))
    )
    (net (code "11") (name "C6") (class "Default")
      (node (ref "D37") (pin "2") (pinfunction "C_2") (pintype "unspecified"))
      (node (ref "D38") (pin "2") (pinfunction "C_2") (pintype "unspecified"))
      (node (ref "D39") (pin "2") (pinfunction "C_2") (pintype "unspecified"))
      (node (ref "D40") (pin "2") (pinfunction "C_2") (pintype "unspecified"))
      (node (ref "D41") (pin "2") (pinfunction "C_2") (pintype "unspecified"))
      (node (ref "D42") (pin "2") (pinfunction "C_2") (pintype "unspecified"))
      (node (ref "U1") (pin "9") (pinfunction "G06_9") (pintype "unspecified"))
    )
    (net (code "12") (name "C7") (class "Default")
      (node (ref "D43") (pin "2") (pinfunction "C_2") (pintype "unspecified"))
      (node (ref "D44") (pin "2") (pinfunction "C_2") (pintype "unspecified"))
      (node (ref "D45") (pin "2") (pinfunction "C_2") (pintype "unspecified"))
      (node (ref "D46") (pin "2") (pinfunction "C_2") (pintype "unspecified"))
      (node (ref "D47") (pin "2") (pinfunction "C_2") (pintype "unspecified"))
      (node (ref "D48") (pin "2") (pinfunction "C_2") (pintype "unspecified"))
      (node (ref "U1") (pin "10") (pinfunction "G07_10") (pintype "unspecified"))
    )
    (net (code "13") (name "C8") (class "Default")
      (node (ref "D49") (pin "2") (pinfunction "C_2") (pintype "unspecified"))
      (node (ref "D50") (pin "2") (pinfunction "C_2") (pintype "unspecified"))
      (node (ref "D51") (pin "2") (pinfunction "C_2") (pintype "unspecified"))
      (node (ref "D52") (pin "2") (pinfunction "C_2") (pintype "unspecified"))
      (node (ref "D53") (pin "2") (pinfunction "C_2") (pintype "unspecified"))
      (node (ref "D54") (pin "2") (pinfunction "C_2") (pintype "unspecified"))
      (node (ref "U1") (pin "11") (pinfunction "G08_11") (pintype "unspecified"))
    )
    (net (code "14") (name "C9") (class "Default")
      (node (ref "D55") (pin "2") (pinfunction "C_2") (pintype "unspecified"))
      (node (ref "D56") (pin "2") (pinfunction "C_2") (pintype "unspecified"))
      (node (ref "D57") (pin "2") (pinfunction "C_2") (pintype "unspecified"))
      (node (ref "D58") (pin "2") (pinfunction "C_2") (pintype "unspecified"))
      (node (ref "D59") (pin "2") (pinfunction "C_2") (pintype "unspecified"))
      (node (ref "D60") (pin "2") (pinfunction "C_2") (pintype "unspecified"))
      (node (ref "U1") (pin "12") (pinfunction "G09_12") (pintype "unspecified"))
    )
    (net (code "15") (name "CS") (class "Default")
      (node (ref "U1") (pin "27") (pinfunction "G21_27") (pintype "unspecified"))
      (node (ref "U4") (pin "3") (pinfunction "3_3") (pintype "input"))
    )
    (net (code "16") (name "DC") (class "Default")
      (node (ref "U1") (pin "29") (pinfunction "G22_29") (pintype "unspecified"))
      (node (ref "U4") (pin "5") (pinfunction "5_5") (pintype "input"))
    )
    (net (code "17") (name "GND") (class "Default")
      (node (ref "C2") (pin "2") (pinfunction "2_2") (pintype "unspecified"))
      (node (ref "C3") (pin "2") (pinfunction "2_2") (pintype "unspecified"))
      (node (ref "C4") (pin "2") (pinfunction "2_2") (pintype "unspecified"))
      (node (ref "R4") (pin "1") (pinfunction "1_1") (pintype "unspecified"))
      (node (ref "U1") (pin "13") (pinfunction "GND_13") (pintype "unspecified"))
      (node (ref "U1") (pin "18") (pinfunction "GND_18") (pintype "unspecified"))
      (node (ref "U1") (pin "23") (pinfunction "GND_23") (pintype "unspecified"))
      (node (ref "U1") (pin "28") (pinfunction "GND_28") (pintype "unspecified"))
      (node (ref "U1") (pin "3") (pinfunction "GND_3") (pintype "unspecified"))
      (node (ref "U1") (pin "33") (pinfunction "GND_33") (pintype "unspecified"))
      (node (ref "U1") (pin "38") (pinfunction "GND_38") (pintype "unspecified"))
      (node (ref "U1") (pin "8") (pinfunction "GND_8") (pintype "unspecified"))
      (node (ref "U2") (pin "7") (pinfunction "GND_7") (pintype "unspecified"))
      (node (ref "U4") (pin "2") (pinfunction "2_2") (pintype "input"))
    )
    (net (code "18") (name "INPLUS") (class "Default")
      (node (ref "R1") (pin "2") (pinfunction "2_2") (pintype "unspecified"))
      (node (ref "U1") (pin "22") (pinfunction "G17_22") (pintype "unspecified"))
    )
    (net (code "19") (name "MISO") (class "Default")
      (node (ref "U1") (pin "26") (pinfunction "G20_26") (pintype "unspecified"))
      (node (ref "U4") (pin "9") (pinfunction "9_9") (pintype "input"))
    )
    (net (code "20") (name "MOSI") (class "Default")
      (node (ref "U1") (pin "25") (pinfunction "G19_25") (pintype "unspecified"))
      (node (ref "U4") (pin "6") (pinfunction "6_6") (pintype "input"))
    )
    (net (code "21") (name "Net-(C1-Pad2)") (class "Default")
      (node (ref "C1") (pin "2") (pinfunction "2_2") (pintype "unspecified"))
      (node (ref "R1") (pin "1") (pinfunction "1_1") (pintype "unspecified"))
    )
    (net (code "22") (name "Net-(D1-A)") (class "Default")
      (node (ref "D1") (pin "1") (pinfunction "A_1") (pintype "unspecified"))
      (node (ref "SW1") (pin "3") (pinfunction "3_3") (pintype "input"))
      (node (ref "SW1") (pin "4") (pinfunction "4_4") (pintype "input"))
    )
    (net (code "23") (name "Net-(D2-A)") (class "Default")
      (node (ref "D2") (pin "1") (pinfunction "A_1") (pintype "unspecified"))
      (node (ref "SW2") (pin "3") (pinfunction "3_3") (pintype "input"))
      (node (ref "SW2") (pin "4") (pinfunction "4_4") (pintype "input"))
    )
    (net (code "24") (name "Net-(D3-A)") (class "Default")
      (node (ref "D3") (pin "1") (pinfunction "A_1") (pintype "unspecified"))
      (node (ref "SW3") (pin "3") (pinfunction "3_3") (pintype "input"))
      (node (ref "SW3") (pin "4") (pinfunction "4_4") (pintype "input"))
    )
    (net (code "25") (name "Net-(D4-A)") (class "Default")
      (node (ref "D4") (pin "1") (pinfunction "A_1") (pintype "unspecified"))
      (node (ref "SW4") (pin "3") (pinfunction "3_3") (pintype "input"))
      (node (ref "SW4") (pin "4") (pinfunction "4_4") (pintype "input"))
    )
    (net (code "26") (name "Net-(D5-A)") (class "Default")
      (node (ref "D5") (pin "1") (pinfunction "A_1") (pintype "unspecified"))
      (node (ref "SW5") (pin "3") (pinfunction "3_3") (pintype "input"))
      (node (ref "SW5") (pin "4") (pinfunction "4_4") (pintype "input"))
    )
    (net (code "27") (name "Net-(D6-A)") (class "Default")
      (node (ref "D6") (pin "1") (pinfunction "A_1") (pintype "unspecified"))
      (node (ref "SW6") (pin "3") (pinfunction "3_3") (pintype "input"))
      (node (ref "SW6") (pin "4") (pinfunction "4_4") (pintype "input"))
    )
    (net (code "28") (name "Net-(D7-A)") (class "Default")
      (node (ref "D7") (pin "1") (pinfunction "A_1") (pintype "unspecified"))
      (node (ref "SW7") (pin "3") (pinfunction "3_3") (pintype "input"))
      (node (ref "SW7") (pin "4") (pinfunction "4_4") (pintype "input"))
    )
    (net (code "29") (name "Net-(D8-A)") (class "Default")
      (node (ref "D8") (pin "1") (pinfunction "A_1") (pintype "unspecified"))
      (node (ref "SW8") (pin "3") (pinfunction "3_3") (pintype "input"))
      (node (ref "SW8") (pin "4") (pinfunction "4_4") (pintype "input"))
    )
    (net (code "30") (name "Net-(D9-A)") (class "Default")
      (node (ref "D9") (pin "1") (pinfunction "A_1") (pintype "unspecified"))
      (node (ref "SW9") (pin "3") (pinfunction "3_3") (pintype "input"))
      (node (ref "SW9") (pin "4") (pinfunction "4_4") (pintype "input"))
    )
    (net (code "31") (name "Net-(D10-A)") (class "Default")
      (node (ref "D10") (pin "1") (pinfunction "A_1") (pintype "unspecified"))
      (node (ref "SW10") (pin "3") (pinfunction "3_3") (pintype "input"))
      (node (ref "SW10") (pin "4") (pinfunction "4_4") (pintype "input"))
    )
    (net (code "32") (name "Net-(D11-A)") (class "Default")
      (node (ref "D11") (pin "1") (pinfunction "A_1") (pintype "unspecified"))
      (node (ref "SW11") (pin "3") (pinfunction "3_3") (pintype "input"))
      (node (ref "SW11") (pin "4") (pinfunction "4_4") (pintype "input"))
    )
    (net (code "33") (name "Net-(D12-A)") (class "Default")
      (node (ref "D12") (pin "1") (pinfunction "A_1") (pintype "unspecified"))
      (node (ref "SW12") (pin "3") (pinfunction "3_3") (pintype "input"))
      (node (ref "SW12") (pin "4") (pinfunction "4_4") (pintype "input"))
    )
    (net (code "34") (name "Net-(D13-A)") (class "Default")
      (node (ref "D13") (pin "1") (pinfunction "A_1") (pintype "unspecified"))
      (node (ref "SW13") (pin "3") (pinfunction "3_3") (pintype "input"))
      (node (ref "SW13") (pin "4") (pinfunction "4_4") (pintype "input"))
    )
    (net (code "35") (name "Net-(D14-A)") (class "Default")
      (node (ref "D14") (pin "1") (pinfunction "A_1") (pintype "unspecified"))
      (node (ref "SW14") (pin "3") (pinfunction "3_3") (pintype "input"))
      (node (ref "SW14") (pin "4") (pinfunction "4_4") (pintype "input"))
    )
    (net (code "36") (name "Net-(D15-A)") (class "Default")
      (node (ref "D15") (pin "1") (pinfunction "A_1") (pintype "unspecified"))
      (node (ref "SW15") (pin "3") (pinfunction "3_3") (pintype "input"))
      (node (ref "SW15") (pin "4") (pinfunction "4_4") (pintype "input"))
    )
    (net (code "37") (name "Net-(D17-A)") (class "Default")
      (node (ref "D17") (pin "1") (pinfunction "A_1") (pintype "unspecified"))
      (node (ref "SW17") (pin "3") (pinfunction "3_3") (pintype "input"))
      (node (ref "SW17") (pin "4") (pinfunction "4_4") (pintype "input"))
    )
    (net (code "38") (name "Net-(D19-A)") (class "Default")
      (node (ref "D19") (pin "1") (pinfunction "A_1") (pintype "unspecified"))
      (node (ref "SW19") (pin "3") (pinfunction "3_3") (pintype "input"))
      (node (ref "SW19") (pin "4") (pinfunction "4_4") (pintype "input"))
    )
    (net (code "39") (name "Net-(D20-A)") (class "Default")
      (node (ref "D20") (pin "1") (pinfunction "A_1") (pintype "unspecified"))
      (node (ref "SW20") (pin "3") (pinfunction "3_3") (pintype "input"))
      (node (ref "SW20") (pin "4") (pinfunction "4_4") (pintype "input"))
    )
    (net (code "40") (name "Net-(D21-A)") (class "Default")
      (node (ref "D21") (pin "1") (pinfunction "A_1") (pintype "unspecified"))
      (node (ref "SW21") (pin "3") (pinfunction "3_3") (pintype "input"))
      (node (ref "SW21") (pin "4") (pinfunction "4_4") (pintype "input"))
    )
    (net (code "41") (name "Net-(D22-A)") (class "Default")
      (node (ref "D22") (pin "1") (pinfunction "A_1") (pintype "unspecified"))
      (node (ref "SW22") (pin "3") (pinfunction "3_3") (pintype "input"))
      (node (ref "SW22") (pin "4") (pinfunction "4_4") (pintype "input"))
    )
    (net (code "42") (name "Net-(D23-A)") (class "Default")
      (node (ref "D23") (pin "1") (pinfunction "A_1") (pintype "unspecified"))
      (node (ref "SW23") (pin "3") (pinfunction "3_3") (pintype "input"))
      (node (ref "SW23") (pin "4") (pinfunction "4_4") (pintype "input"))
    )
    (net (code "43") (name "Net-(D24-A)") (class "Default")
      (node (ref "D24") (pin "1") (pinfunction "A_1") (pintype "unspecified"))
      (node (ref "SW24") (pin "3") (pinfunction "3_3") (pintype "input"))
      (node (ref "SW24") (pin "4") (pinfunction "4_4") (pintype "input"))
    )
    (net (code "44") (name "Net-(D25-A)") (class "Default")
      (node (ref "D25") (pin "1") (pinfunction "A_1") (pintype "unspecified"))
      (node (ref "SW25") (pin "3") (pinfunction "3_3") (pintype "input"))
      (node (ref "SW25") (pin "4") (pinfunction "4_4") (pintype "input"))
    )
    (net (code "45") (name "Net-(D26-A)") (class "Default")
      (node (ref "D26") (pin "1") (pinfunction "A_1") (pintype "unspecified"))
      (node (ref "SW26") (pin "3") (pinfunction "3_3") (pintype "input"))
      (node (ref "SW26") (pin "4") (pinfunction "4_4") (pintype "input"))
    )
    (net (code "46") (name "Net-(D27-A)") (class "Default")
      (node (ref "D27") (pin "1") (pinfunction "A_1") (pintype "unspecified"))
      (node (ref "SW27") (pin "3") (pinfunction "3_3") (pintype "input"))
      (node (ref "SW27") (pin "4") (pinfunction "4_4") (pintype "input"))
    )
    (net (code "47") (name "Net-(D28-A)") (class "Default")
      (node (ref "D28") (pin "1") (pinfunction "A_1") (pintype "unspecified"))
      (node (ref "SW28") (pin "3") (pinfunction "3_3") (pintype "input"))
      (node (ref "SW28") (pin "4") (pinfunction "4_4") (pintype "input"))
    )
    (net (code "48") (name "Net-(D29-A)") (class "Default")
      (node (ref "D29") (pin "1") (pinfunction "A_1") (pintype "unspecified"))
      (node (ref "SW29") (pin "3") (pinfunction "3_3") (pintype "input"))
      (node (ref "SW29") (pin "4") (pinfunction "4_4") (pintype "input"))
    )
    (net (code "49") (name "Net-(D30-A)") (class "Default")
      (node (ref "D30") (pin "1") (pinfunction "A_1") (pintype "unspecified"))
      (node (ref "SW30") (pin "3") (pinfunction "3_3") (pintype "input"))
      (node (ref "SW30") (pin "4") (pinfunction "4_4") (pintype "input"))
    )
    (net (code "50") (name "Net-(D31-A)") (class "Default")
      (node (ref "D31") (pin "1") (pinfunction "A_1") (pintype "unspecified"))
      (node (ref "SW31") (pin "3") (pinfunction "3_3") (pintype "input"))
      (node (ref "SW31") (pin "4") (pinfunction "4_4") (pintype "input"))
    )
    (net (code "51") (name "Net-(D32-A)") (class "Default")
      (node (ref "D32") (pin "1") (pinfunction "A_1") (pintype "unspecified"))
      (node (ref "SW32") (pin "3") (pinfunction "3_3") (pintype "input"))
      (node (ref "SW32") (pin "4") (pinfunction "4_4") (pintype "input"))
    )
    (net (code "52") (name "Net-(D33-A)") (class "Default")
      (node (ref "D33") (pin "1") (pinfunction "A_1") (pintype "unspecified"))
      (node (ref "SW33") (pin "3") (pinfunction "3_3") (pintype "input"))
      (node (ref "SW33") (pin "4") (pinfunction "4_4") (pintype "input"))
    )
    (net (code "53") (name "Net-(D34-A)") (class "Default")
      (node (ref "D34") (pin "1") (pinfunction "A_1") (pintype "unspecified"))
      (node (ref "SW34") (pin "3") (pinfunction "3_3") (pintype "input"))
      (node (ref "SW34") (pin "4") (pinfunction "4_4") (pintype "input"))
    )
    (net (code "54") (name "Net-(D35-A)") (class "Default")
      (node (ref "D35") (pin "1") (pinfunction "A_1") (pintype "unspecified"))
      (node (ref "SW35") (pin "3") (pinfunction "3_3") (pintype "input"))
      (node (ref "SW35") (pin "4") (pinfunction "4_4") (pintype "input"))
    )
    (net (code "55") (name "Net-(D36-A)") (class "Default")
      (node (ref "D36") (pin "1") (pinfunction "A_1") (pintype "unspecified"))
      (node (ref "SW36") (pin "3") (pinfunction "3_3") (pintype "input"))
      (node (ref "SW36") (pin "4") (pinfunction "4_4") (pintype "input"))
    )
    (net (code "56") (name "Net-(D37-A)") (class "Default")
      (node (ref "D37") (pin "1") (pinfunction "A_1") (pintype "unspecified"))
      (node (ref "SW37") (pin "3") (pinfunction "3_3") (pintype "input"))
      (node (ref "SW37") (pin "4") (pinfunction "4_4") (pintype "input"))
    )
    (net (code "57") (name "Net-(D38-A)") (class "Default")
      (node (ref "D38") (pin "1") (pinfunction "A_1") (pintype "unspecified"))
      (node (ref "SW38") (pin "3") (pinfunction "3_3") (pintype "input"))
      (node (ref "SW38") (pin "4") (pinfunction "4_4") (pintype "input"))
    )
    (net (code "58") (name "Net-(D39-A)") (class "Default")
      (node (ref "D39") (pin "1") (pinfunction "A_1") (pintype "unspecified"))
      (node (ref "SW39") (pin "3") (pinfunction "3_3") (pintype "input"))
      (node (ref "SW39") (pin "4") (pinfunction "4_4") (pintype "input"))
    )
    (net (code "59") (name "Net-(D40-A)") (class "Default")
      (node (ref "D40") (pin "1") (pinfunction "A_1") (pintype "unspecified"))
      (node (ref "SW40") (pin "3") (pinfunction "3_3") (pintype "input"))
      (node (ref "SW40") (pin "4") (pinfunction "4_4") (pintype "input"))
    )
    (net (code "60") (name "Net-(D41-A)") (class "Default")
      (node (ref "D41") (pin "1") (pinfunction "A_1") (pintype "unspecified"))
      (node (ref "SW41") (pin "3") (pinfunction "3_3") (pintype "input"))
      (node (ref "SW41") (pin "4") (pinfunction "4_4") (pintype "input"))
    )
    (net (code "61") (name "Net-(D42-A)") (class "Default")
      (node (ref "D42") (pin "1") (pinfunction "A_1") (pintype "unspecified"))
      (node (ref "SW42") (pin "3") (pinfunction "3_3") (pintype "input"))
      (node (ref "SW42") (pin "4") (pinfunction "4_4") (pintype "input"))
    )
    (net (code "62") (name "Net-(D43-A)") (class "Default")
      (node (ref "D43") (pin "1") (pinfunction "A_1") (pintype "unspecified"))
      (node (ref "SW43") (pin "3") (pinfunction "3_3") (pintype "input"))
      (node (ref "SW43") (pin "4") (pinfunction "4_4") (pintype "input"))
    )
    (net (code "63") (name "Net-(D44-A)") (class "Default")
      (node (ref "D44") (pin "1") (pinfunction "A_1") (pintype "unspecified"))
      (node (ref "SW44") (pin "3") (pinfunction "3_3") (pintype "input"))
      (node (ref "SW44") (pin "4") (pinfunction "4_4") (pintype "input"))
    )
    (net (code "64") (name "Net-(D45-A)") (class "Default")
      (node (ref "D45") (pin "1") (pinfunction "A_1") (pintype "unspecified"))
      (node (ref "SW45") (pin "3") (pinfunction "3_3") (pintype "input"))
      (node (ref "SW45") (pin "4") (pinfunction "4_4") (pintype "input"))
    )
    (net (code "65") (name "Net-(D46-A)") (class "Default")
      (node (ref "D46") (pin "1") (pinfunction "A_1") (pintype "unspecified"))
      (node (ref "SW46") (pin "3") (pinfunction "3_3") (pintype "input"))
      (node (ref "SW46") (pin "4") (pinfunction "4_4") (pintype "input"))
    )
    (net (code "66") (name "Net-(D47-A)") (class "Default")
      (node (ref "D47") (pin "1") (pinfunction "A_1") (pintype "unspecified"))
      (node (ref "SW47") (pin "3") (pinfunction "3_3") (pintype "input"))
      (node (ref "SW47") (pin "4") (pinfunction "4_4") (pintype "input"))
    )
    (net (code "67") (name "Net-(D48-A)") (class "Default")
      (node (ref "D48") (pin "1") (pinfunction "A_1") (pintype "unspecified"))
      (node (ref "SW48") (pin "3") (pinfunction "3_3") (pintype "input"))
      (node (ref "SW48") (pin "4") (pinfunction "4_4") (pintype "input"))
    )
    (net (code "68") (name "Net-(D49-A)") (class "Default")
      (node (ref "D49") (pin "1") (pinfunction "A_1") (pintype "unspecified"))
      (node (ref "SW49") (pin "3") (pinfunction "3_3") (pintype "input"))
      (node (ref "SW49") (pin "4") (pinfunction "4_4") (pintype "input"))
    )
    (net (code "69") (name "Net-(D50-A)") (class "Default")
      (node (ref "D50") (pin "1") (pinfunction "A_1") (pintype "unspecified"))
      (node (ref "SW50") (pin "3") (pinfunction "3_3") (pintype "input"))
      (node (ref "SW50") (pin "4") (pinfunction "4_4") (pintype "input"))
    )
    (net (code "70") (name "Net-(D51-A)") (class "Default")
      (node (ref "D51") (pin "1") (pinfunction "A_1") (pintype "unspecified"))
      (node (ref "SW51") (pin "3") (pinfunction "3_3") (pintype "input"))
      (node (ref "SW51") (pin "4") (pinfunction "4_4") (pintype "input"))
    )
    (net (code "71") (name "Net-(D52-A)") (class "Default")
      (node (ref "D52") (pin "1") (pinfunction "A_1") (pintype "unspecified"))
      (node (ref "SW52") (pin "3") (pinfunction "3_3") (pintype "input"))
      (node (ref "SW52") (pin "4") (pinfunction "4_4") (pintype "input"))
    )
    (net (code "72") (name "Net-(D53-A)") (class "Default")
      (node (ref "D53") (pin "1") (pinfunction "A_1") (pintype "unspecified"))
      (node (ref "SW53") (pin "3") (pinfunction "3_3") (pintype "input"))
      (node (ref "SW53") (pin "4") (pinfunction "4_4") (pintype "input"))
    )
    (net (code "73") (name "Net-(D54-A)") (class "Default")
      (node (ref "D54") (pin "1") (pinfunction "A_1") (pintype "unspecified"))
      (node (ref "SW54") (pin "3") (pinfunction "3_3") (pintype "input"))
      (node (ref "SW54") (pin "4") (pinfunction "4_4") (pintype "input"))
    )
    (net (code "74") (name "Net-(D55-A)") (class "Default")
      (node (ref "D55") (pin "1") (pinfunction "A_1") (pintype "unspecified"))
      (node (ref "SW55") (pin "3") (pinfunction "3_3") (pintype "input"))
      (node (ref "SW55") (pin "4") (pinfunction "4_4") (pintype "input"))
    )
    (net (code "75") (name "Net-(D56-A)") (class "Default")
      (node (ref "D56") (pin "1") (pinfunction "A_1") (pintype "unspecified"))
      (node (ref "SW56") (pin "3") (pinfunction "3_3") (pintype "input"))
      (node (ref "SW56") (pin "4") (pinfunction "4_4") (pintype "input"))
    )
    (net (code "76") (name "Net-(D57-A)") (class "Default")
      (node (ref "D57") (pin "1") (pinfunction "A_1") (pintype "unspecified"))
      (node (ref "SW57") (pin "3") (pinfunction "3_3") (pintype "input"))
      (node (ref "SW57") (pin "4") (pinfunction "4_4") (pintype "input"))
    )
    (net (code "77") (name "Net-(D58-A)") (class "Default")
      (node (ref "D58") (pin "1") (pinfunction "A_1") (pintype "unspecified"))
      (node (ref "SW58") (pin "3") (pinfunction "3_3") (pintype "input"))
      (node (ref "SW58") (pin "4") (pinfunction "4_4") (pintype "input"))
    )
    (net (code "78") (name "Net-(D59-A)") (class "Default")
      (node (ref "D59") (pin "1") (pinfunction "A_1") (pintype "unspecified"))
      (node (ref "SW59") (pin "3") (pinfunction "3_3") (pintype "input"))
      (node (ref "SW59") (pin "4") (pinfunction "4_4") (pintype "input"))
    )
    (net (code "79") (name "Net-(D60-A)") (class "Default")
      (node (ref "D60") (pin "1") (pinfunction "A_1") (pintype "unspecified"))
      (node (ref "SW60") (pin "3") (pinfunction "3_3") (pintype "input"))
      (node (ref "SW60") (pin "4") (pinfunction "4_4") (pintype "input"))
    )
    (net (code "80") (name "Net-(Q1-B)") (class "Default")
      (node (ref "Q1") (pin "1") (pinfunction "B_1") (pintype "unspecified"))
      (node (ref "R2") (pin "1") (pinfunction "1_1") (pintype "unspecified"))
      (node (ref "R3") (pin "1") (pinfunction "1_1") (pintype "unspecified"))
    )
    (net (code "81") (name "Net-(SPK1-+)") (class "Default")
      (node (ref "SPK1") (pin "1") (pinfunction "+_1") (pintype "unspecified"))
      (node (ref "U2") (pin "5") (pinfunction "VO+_5") (pintype "output"))
    )
    (net (code "82") (name "Net-(SPK1--)") (class "Default")
      (node (ref "SPK1") (pin "2") (pinfunction "-_2") (pintype "unspecified"))
      (node (ref "U2") (pin "8") (pinfunction "VO-_8") (pintype "unspecified"))
    )
    (net (code "83") (name "Net-(U2-IN+)") (class "Default")
      (node (ref "C1") (pin "1") (pinfunction "1_1") (pintype "unspecified"))
      (node (ref "U2") (pin "3") (pinfunction "IN+_3") (pintype "unspecified"))
    )
    (net (code "84") (name "Net-(U2-IN-)") (class "Default")
      (node (ref "C2") (pin "1") (pinfunction "1_1") (pintype "unspecified"))
      (node (ref "U2") (pin "4") (pinfunction "IN-_4") (pintype "unspecified"))
    )
    (net (code "85") (name "R0") (class "Default")
      (node (ref "SW1") (pin "1") (pinfunction "1_1") (pintype "input"))
      (node (ref "SW1") (pin "2") (pinfunction "2_2") (pintype "input"))
      (node (ref "SW13") (pin "1") (pinfunction "1_1") (pintype "input"))
      (node (ref "SW13") (pin "2") (pinfunction "2_2") (pintype "input"))
      (node (ref "SW19") (pin "1") (pinfunction "1_1") (pintype "input"))
      (node (ref "SW19") (pin "2") (pinfunction "2_2") (pintype "input"))
      (node (ref "SW25") (pin "1") (pinfunction "1_1") (pintype "input"))
      (node (ref "SW25") (pin "2") (pinfunction "2_2") (pintype "input"))
      (node (ref "SW31") (pin "1") (pinfunction "1_1") (pintype "input"))
      (node (ref "SW31") (pin "2") (pinfunction "2_2") (pintype "input"))
      (node (ref "SW37") (pin "1") (pinfunction "1_1") (pintype "input"))
      (node (ref "SW37") (pin "2") (pinfunction "2_2") (pintype "input"))
      (node (ref "SW43") (pin "1") (pinfunction "1_1") (pintype "input"))
      (node (ref "SW43") (pin "2") (pinfunction "2_2") (pintype "input"))
      (node (ref "SW49") (pin "1") (pinfunction "1_1") (pintype "input"))
      (node (ref "SW49") (pin "2") (pinfunction "2_2") (pintype "input"))
      (node (ref "SW55") (pin "1") (pinfunction "1_1") (pintype "input"))
      (node (ref "SW55") (pin "2") (pinfunction "2_2") (pintype "input"))
      (node (ref "SW7") (pin "1") (pinfunction "1_1") (pintype "input"))
      (node (ref "SW7") (pin "2") (pinfunction "2_2") (pintype "input"))
      (node (ref "U1") (pin "14") (pinfunction "G10_14") (pintype "unspecified"))
    )
    (net (code "86") (name "R1") (class "Default")
      (node (ref "SW14") (pin "1") (pinfunction "1_1") (pintype "input"))
      (node (ref "SW14") (pin "2") (pinfunction "2_2") (pintype "input"))
      (node (ref "SW2") (pin "1") (pinfunction "1_1") (pintype "input"))
      (node (ref "SW2") (pin "2") (pinfunction "2_2") (pintype "input"))
      (node (ref "SW20") (pin "1") (pinfunction "1_1") (pintype "input"))
      (node (ref "SW20") (pin "2") (pinfunction "2_2") (pintype "input"))
      (node (ref "SW26") (pin "1") (pinfunction "1_1") (pintype "input"))
      (node (ref "SW26") (pin "2") (pinfunction "2_2") (pintype "input"))
      (node (ref "SW32") (pin "1") (pinfunction "1_1") (pintype "input"))
      (node (ref "SW32") (pin "2") (pinfunction "2_2") (pintype "input"))
      (node (ref "SW38") (pin "1") (pinfunction "1_1") (pintype "input"))
      (node (ref "SW38") (pin "2") (pinfunction "2_2") (pintype "input"))
      (node (ref "SW44") (pin "1") (pinfunction "1_1") (pintype "input"))
      (node (ref "SW44") (pin "2") (pinfunction "2_2") (pintype "input"))
      (node (ref "SW50") (pin "1") (pinfunction "1_1") (pintype "input"))
      (node (ref "SW50") (pin "2") (pinfunction "2_2") (pintype "input"))
      (node (ref "SW56") (pin "1") (pinfunction "1_1") (pintype "input"))
      (node (ref "SW56") (pin "2") (pinfunction "2_2") (pintype "input"))
      (node (ref "SW8") (pin "1") (pinfunction "1_1") (pintype "input"))
      (node (ref "SW8") (pin "2") (pinfunction "2_2") (pintype "input"))
      (node (ref "U1") (pin "15") (pinfunction "G11_15") (pintype "unspecified"))
    )
    (net (code "87") (name "R2") (class "Default")
      (node (ref "SW15") (pin "1") (pinfunction "1_1") (pintype "input"))
      (node (ref "SW15") (pin "2") (pinfunction "2_2") (pintype "input"))
      (node (ref "SW21") (pin "1") (pinfunction "1_1") (pintype "input"))
      (node (ref "SW21") (pin "2") (pinfunction "2_2") (pintype "input"))
      (node (ref "SW27") (pin "1") (pinfunction "1_1") (pintype "input"))
      (node (ref "SW27") (pin "2") (pinfunction "2_2") (pintype "input"))
      (node (ref "SW3") (pin "1") (pinfunction "1_1") (pintype "input"))
      (node (ref "SW3") (pin "2") (pinfunction "2_2") (pintype "input"))
      (node (ref "SW33") (pin "1") (pinfunction "1_1") (pintype "input"))
      (node (ref "SW33") (pin "2") (pinfunction "2_2") (pintype "input"))
      (node (ref "SW39") (pin "1") (pinfunction "1_1") (pintype "input"))
      (node (ref "SW39") (pin "2") (pinfunction "2_2") (pintype "input"))
      (node (ref "SW45") (pin "1") (pinfunction "1_1") (pintype "input"))
      (node (ref "SW45") (pin "2") (pinfunction "2_2") (pintype "input"))
      (node (ref "SW51") (pin "1") (pinfunction "1_1") (pintype "input"))
      (node (ref "SW51") (pin "2") (pinfunction "2_2") (pintype "input"))
      (node (ref "SW57") (pin "1") (pinfunction "1_1") (pintype "input"))
      (node (ref "SW57") (pin "2") (pinfunction "2_2") (pintype "input"))
      (node (ref "SW9") (pin "1") (pinfunction "1_1") (pintype "input"))
      (node (ref "SW9") (pin "2") (pinfunction "2_2") (pintype "input"))
      (node (ref "U1") (pin "16") (pinfunction "G12_16") (pintype "unspecified"))
    )
    (net (code "88") (name "R3") (class "Default")
      (node (ref "SW10") (pin "1") (pinfunction "1_1") (pintype "input"))
      (node (ref "SW10") (pin "2") (pinfunction "2_2") (pintype "input"))
      (node (ref "SW22") (pin "1") (pinfunction "1_1") (pintype "input"))
      (node (ref "SW22") (pin "2") (pinfunction "2_2") (pintype "input"))
      (node (ref "SW28") (pin "1") (pinfunction "1_1") (pintype "input"))
      (node (ref "SW28") (pin "2") (pinfunction "2_2") (pintype "input"))
      (node (ref "SW34") (pin "1") (pinfunction "1_1") (pintype "input"))
      (node (ref "SW34") (pin "2") (pinfunction "2_2") (pintype "input"))
      (node (ref "SW4") (pin "1") (pinfunction "1_1") (pintype "input"))
      (node (ref "SW4") (pin "2") (pinfunction "2_2") (pintype "input"))
      (node (ref "SW40") (pin "1") (pinfunction "1_1") (pintype "input"))
      (node (ref "SW40") (pin "2") (pinfunction "2_2") (pintype "input"))
      (node (ref "SW46") (pin "1") (pinfunction "1_1") (pintype "input"))
      (node (ref "SW46") (pin "2") (pinfunction "2_2") (pintype "input"))
      (node (ref "SW52") (pin "1") (pinfunction "1_1") (pintype "input"))
      (node (ref "SW52") (pin "2") (pinfunction "2_2") (pintype "input"))
      (node (ref "SW58") (pin "1") (pinfunction "1_1") (pintype "input"))
      (node (ref "SW58") (pin "2") (pinfunction "2_2") (pintype "input"))
      (node (ref "U1") (pin "17") (pinfunction "G13_17") (pintype "unspecified"))
    )
    (net (code "89") (name "R4") (class "Default")
      (node (ref "SW11") (pin "1") (pinfunction "1_1") (pintype "input"))
      (node (ref "SW11") (pin "2") (pinfunction "2_2") (pintype "input"))
      (node (ref "SW17") (pin "1") (pinfunction "1_1") (pintype "input"))
      (node (ref "SW17") (pin "2") (pinfunction "2_2") (pintype "input"))
      (node (ref "SW23") (pin "1") (pinfunction "1_1") (pintype "input"))
      (node (ref "SW23") (pin "2") (pinfunction "2_2") (pintype "input"))
      (node (ref "SW29") (pin "1") (pinfunction "1_1") (pintype "input"))
      (node (ref "SW29") (pin "2") (pinfunction "2_2") (pintype "input"))
      (node (ref "SW35") (pin "1") (pinfunction "1_1") (pintype "input"))
      (node (ref "SW35") (pin "2") (pinfunction "2_2") (pintype "input"))
      (node (ref "SW41") (pin "1") (pinfunction "1_1") (pintype "input"))
      (node (ref "SW41") (pin "2") (pinfunction "2_2") (pintype "input"))
      (node (ref "SW47") (pin "1") (pinfunction "1_1") (pintype "input"))
      (node (ref "SW47") (pin "2") (pinfunction "2_2") (pintype "input"))
      (node (ref "SW5") (pin "1") (pinfunction "1_1") (pintype "input"))
      (node (ref "SW5") (pin "2") (pinfunction "2_2") (pintype "input"))
      (node (ref "SW53") (pin "1") (pinfunction "1_1") (pintype "input"))
      (node (ref "SW53") (pin "2") (pinfunction "2_2") (pintype "input"))
      (node (ref "SW59") (pin "1") (pinfunction "1_1") (pintype "input"))
      (node (ref "SW59") (pin "2") (pinfunction "2_2") (pintype "input"))
      (node (ref "U1") (pin "19") (pinfunction "G14_19") (pintype "unspecified"))
    )
    (net (code "90") (name "R5") (class "Default")
      (node (ref "SW12") (pin "1") (pinfunction "1_1") (pintype "input"))
      (node (ref "SW12") (pin "2") (pinfunction "2_2") (pintype "input"))
      (node (ref "SW24") (pin "1") (pinfunction "1_1") (pintype "input"))
      (node (ref "SW24") (pin "2") (pinfunction "2_2") (pintype "input"))
      (node (ref "SW30") (pin "1") (pinfunction "1_1") (pintype "input"))
      (node (ref "SW30") (pin "2") (pinfunction "2_2") (pintype "input"))
      (node (ref "SW36") (pin "1") (pinfunction "1_1") (pintype "input"))
      (node (ref "SW36") (pin "2") (pinfunction "2_2") (pintype "input"))
      (node (ref "SW42") (pin "1") (pinfunction "1_1") (pintype "input"))
      (node (ref "SW42") (pin "2") (pinfunction "2_2") (pintype "input"))
      (node (ref "SW48") (pin "1") (pinfunction "1_1") (pintype "input"))
      (node (ref "SW48") (pin "2") (pinfunction "2_2") (pintype "input"))
      (node (ref "SW54") (pin "1") (pinfunction "1_1") (pintype "input"))
      (node (ref "SW54") (pin "2") (pinfunction "2_2") (pintype "input"))
      (node (ref "SW6") (pin "1") (pinfunction "1_1") (pintype "input"))
      (node (ref "SW6") (pin "2") (pinfunction "2_2") (pintype "input"))
      (node (ref "SW60") (pin "1") (pinfunction "1_1") (pintype "input"))
      (node (ref "SW60") (pin "2") (pinfunction "2_2") (pintype "input"))
      (node (ref "U1") (pin "20") (pinfunction "G15_20") (pintype "unspecified"))
    )
    (net (code "91") (name "RST") (class "Default")
      (node (ref "U1") (pin "31") (pinfunction "G26_31") (pintype "unspecified"))
      (node (ref "U4") (pin "4") (pinfunction "4_4") (pintype "input"))
    )
    (net (code "92") (name "SCK") (class "Default")
      (node (ref "U1") (pin "24") (pinfunction "G18_24") (pintype "unspecified"))
      (node (ref "U4") (pin "7") (pinfunction "7_7") (pintype "input"))
    )
    (net (code "93") (name "unconnected-(U1-3V3_EN-Pad37)") (class "Default")
      (node (ref "U1") (pin "37") (pinfunction "3V3_EN_37") (pintype "unspecified+no_connect"))
    )
    (net (code "94") (name "unconnected-(U1-G27-Pad32)") (class "Default")
      (node (ref "U1") (pin "32") (pinfunction "G27_32") (pintype "unspecified+no_connect"))
    )
    (net (code "95") (name "unconnected-(U1-RUN-Pad30)") (class "Default")
      (node (ref "U1") (pin "30") (pinfunction "RUN_30") (pintype "unspecified+no_connect"))
    )
    (net (code "96") (name "unconnected-(U1-VBUS-Pad40)") (class "Default")
      (node (ref "U1") (pin "40") (pinfunction "VBUS_40") (pintype "unspecified+no_connect"))
    )
    (net (code "97") (name "unconnected-(U1-VREF-Pad35)") (class "Default")
      (node (ref "U1") (pin "35") (pinfunction "VREF_35") (pintype "unspecified+no_connect"))
    )
    (net (code "98") (name "unconnected-(U1-VSYS-Pad39)") (class "Default")
      (node (ref "U1") (pin "39") (pinfunction "VSYS_39") (pintype "unspecified+no_connect"))
    )
    (net (code "99") (name "unconnected-(U2-NC-Pad2)") (class "Default")
      (node (ref "U2") (pin "2") (pinfunction "NC_2") (pintype "unspecified+no_connect"))
    )
    (net (code "100") (name "unconnected-(U4-Pad10)") (class "Default")
      (node (ref "U4") (pin "10") (pinfunction "10_10") (pintype "input+no_connect"))
    )
    (net (code "101") (name "unconnected-(U4-Pad11)") (class "Default")
      (node (ref "U4") (pin "11") (pinfunction "11_11") (pintype "input+no_connect"))
    )
    (net (code "102") (name "unconnected-(U4-Pad12)") (class "Default")
      (node (ref "U4") (pin "12") (pinfunction "12_12") (pintype "input+no_connect"))
    )
    (net (code "103") (name "unconnected-(U4-Pad13)") (class "Default")
      (node (ref "U4") (pin "13") (pinfunction "13_13") (pintype "input+no_connect"))
    )
    (net (code "104") (name "unconnected-(U4-Pad14)") (class "Default")
      (node (ref "U4") (pin "14") (pinfunction "14_14") (pintype "input+no_connect"))
    )
  )
)
